# AudioStage.net
KiCad netlist of a schematic drawn in Altium Designer
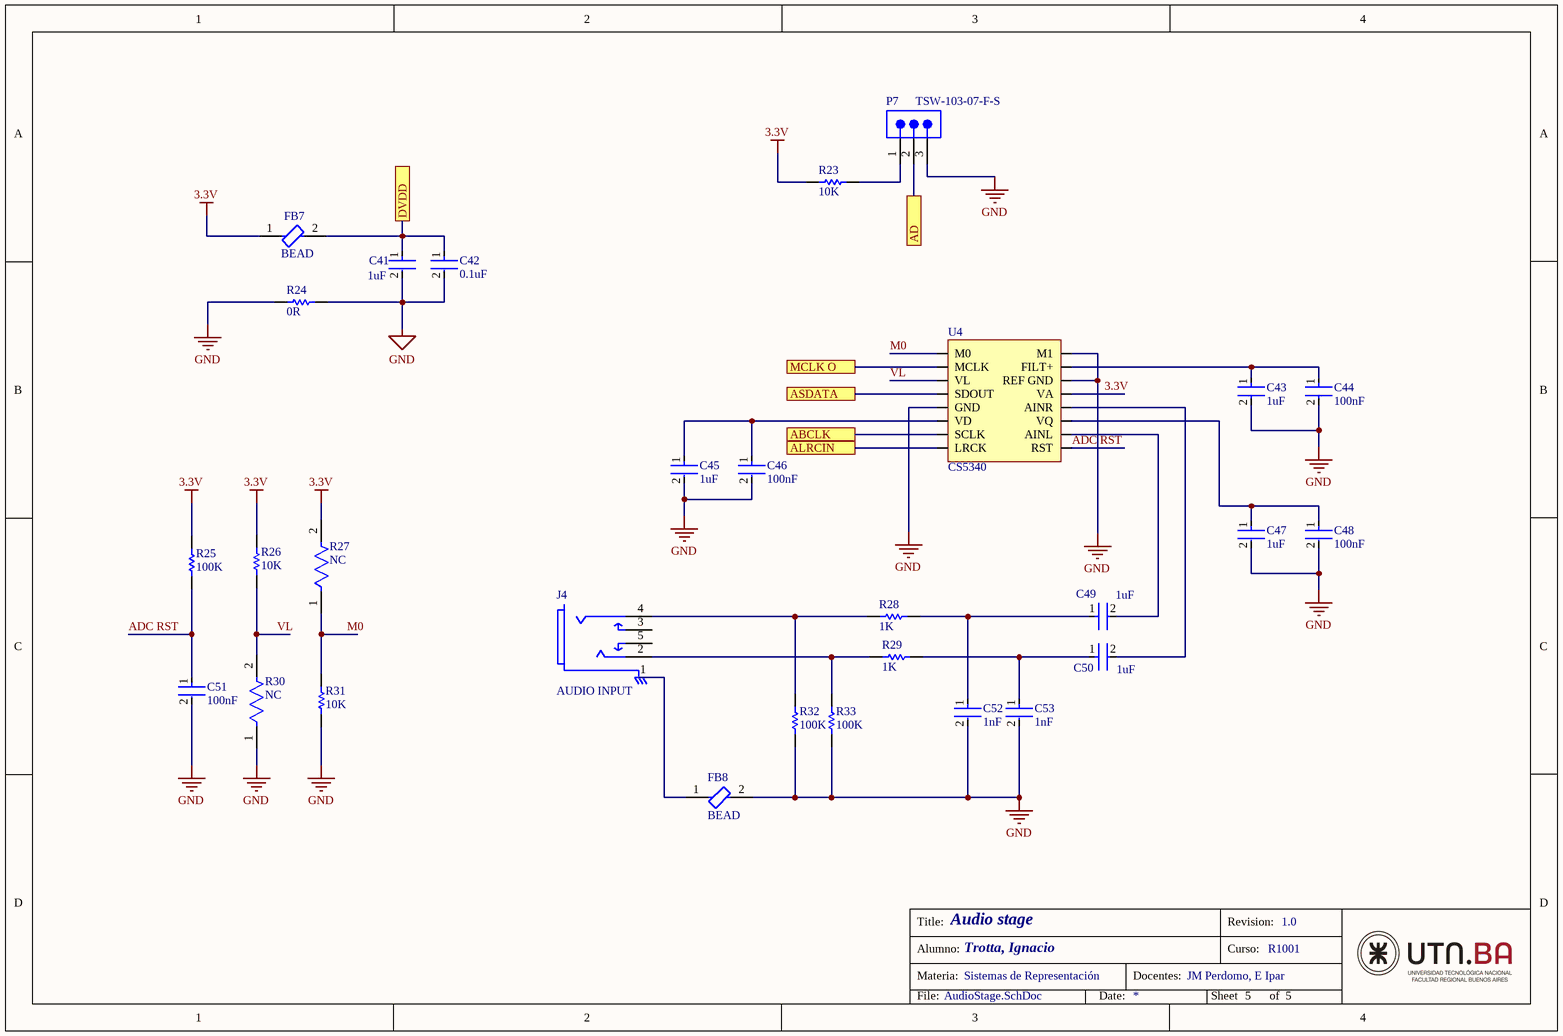
[diagram p0: AudioStage.SchDoc]

(export (version "E")
  (design (tool "Eeschema 10.0.6"))
  (components
    (comp (ref "C41")
      (value "1uF")
      (footprint "FP-CC0603-DA-MFG")
      (description "CAP CER 10000PF 50V X7R 0603")
      (fields (field (name "TOLERANCE") "0.1") (field (name "MANUFACTURER PART NUMBER") "CC0603KRX7R9BB103"))
      (libsource (lib "Altium Content Vault") (part "11868f565c42a9108669ba33697ecf6"))
    )
    (comp (ref "C42")
      (value "0.1uF")
      (footprint "FP-CC0603-DA-MFG")
      (description "CAP CER 10000PF 50V X7R 0603")
      (fields (field (name "TOLERANCE") "0.1") (field (name "MANUFACTURER PART NUMBER") "CC0603KRX7R9BB103"))
      (libsource (lib "Altium Content Vault") (part "11868f565c42a9108669ba33697ecf6"))
    )
    (comp (ref "C43")
      (value "1uF")
      (footprint "FP-CC0603-DA-MFG")
      (description "CAP CER 10000PF 50V X7R 0603")
      (fields (field (name "TOLERANCE") "0.1") (field (name "MANUFACTURER PART NUMBER") "CC0603KRX7R9BB103"))
      (libsource (lib "Altium Content Vault") (part "11868f565c42a9108669ba33697ecf6"))
    )
    (comp (ref "C44")
      (value "100nF")
      (footprint "FP-CC0603-DA-MFG")
      (description "CAP CER 10000PF 50V X7R 0603")
      (fields (field (name "TOLERANCE") "0.1") (field (name "MANUFACTURER PART NUMBER") "CC0603KRX7R9BB103"))
      (libsource (lib "Altium Content Vault") (part "11868f565c42a9108669ba33697ecf6"))
    )
    (comp (ref "C45")
      (value "1uF")
      (footprint "FP-CC0603-DA-MFG")
      (description "CAP CER 10000PF 50V X7R 0603")
      (fields (field (name "TOLERANCE") "0.1") (field (name "MANUFACTURER PART NUMBER") "CC0603KRX7R9BB103"))
      (libsource (lib "Altium Content Vault") (part "11868f565c42a9108669ba33697ecf6"))
    )
    (comp (ref "C46")
      (value "100nF")
      (footprint "FP-CC0603-DA-MFG")
      (description "CAP CER 10000PF 50V X7R 0603")
      (fields (field (name "TOLERANCE") "0.1") (field (name "MANUFACTURER PART NUMBER") "CC0603KRX7R9BB103"))
      (libsource (lib "Altium Content Vault") (part "11868f565c42a9108669ba33697ecf6"))
    )
    (comp (ref "C47")
      (value "1uF")
      (footprint "FP-CC0603-DA-MFG")
      (description "CAP CER 10000PF 50V X7R 0603")
      (fields (field (name "TOLERANCE") "0.1") (field (name "MANUFACTURER PART NUMBER") "CC0603KRX7R9BB103"))
      (libsource (lib "Altium Content Vault") (part "11868f565c42a9108669ba33697ecf6"))
    )
    (comp (ref "C48")
      (value "100nF")
      (footprint "FP-CC0603-DA-MFG")
      (description "CAP CER 10000PF 50V X7R 0603")
      (fields (field (name "TOLERANCE") "0.1") (field (name "MANUFACTURER PART NUMBER") "CC0603KRX7R9BB103"))
      (libsource (lib "Altium Content Vault") (part "11868f565c42a9108669ba33697ecf6"))
    )
    (comp (ref "C49")
      (value "1uF")
      (footprint "FP-CC0603-DA-MFG")
      (description "CAP CER 10000PF 50V X7R 0603")
      (fields (field (name "TOLERANCE") "0.1") (field (name "MANUFACTURER PART NUMBER") "CC0603KRX7R9BB103"))
      (libsource (lib "Altium Content Vault") (part "11868f565c42a9108669ba33697ecf6"))
    )
    (comp (ref "C50")
      (value "1uF")
      (footprint "FP-CC0603-DA-MFG")
      (description "CAP CER 10000PF 50V X7R 0603")
      (fields (field (name "TOLERANCE") "0.1") (field (name "MANUFACTURER PART NUMBER") "CC0603KRX7R9BB103"))
      (libsource (lib "Altium Content Vault") (part "11868f565c42a9108669ba33697ecf6"))
    )
    (comp (ref "C51")
      (value "100nF")
      (footprint "FP-CC0603-DA-MFG")
      (description "CAP CER 10000PF 50V X7R 0603")
      (fields (field (name "TOLERANCE") "0.1") (field (name "MANUFACTURER PART NUMBER") "CC0603KRX7R9BB103"))
      (libsource (lib "Altium Content Vault") (part "11868f565c42a9108669ba33697ecf6"))
    )
    (comp (ref "C52")
      (value "1nF")
      (footprint "FP-CC0603-DA-MFG")
      (description "CAP CER 10000PF 50V X7R 0603")
      (fields (field (name "TOLERANCE") "0.1") (field (name "MANUFACTURER PART NUMBER") "CC0603KRX7R9BB103"))
      (libsource (lib "Altium Content Vault") (part "11868f565c42a9108669ba33697ecf6"))
    )
    (comp (ref "C53")
      (value "1nF")
      (footprint "FP-CC0603-DA-MFG")
      (description "CAP CER 10000PF 50V X7R 0603")
      (fields (field (name "TOLERANCE") "0.1") (field (name "MANUFACTURER PART NUMBER") "CC0603KRX7R9BB103"))
      (libsource (lib "Altium Content Vault") (part "11868f565c42a9108669ba33697ecf6"))
    )
    (comp (ref "FB7")
      (value "BEAD")
      (footprint "FP-BLM18-0_15-t0_8-IPC_B")
      (description "Chip Ferrite Bead, 0603, 75Ω @ 100MHz, 0.3Ω, 25%, 600mA")
      (fields (field (name "TOLERANCE") "25%"))
      (libsource (lib "Altium Content Vault") (part "5f30dd21d616792df468990f7003faa"))
    )
    (comp (ref "FB8")
      (value "BEAD")
      (footprint "FP-BLM18-0_15-t0_8-IPC_B")
      (description "Chip Ferrite Bead, 0603, 75Ω @ 100MHz, 0.3Ω, 25%, 600mA")
      (fields (field (name "TOLERANCE") "25%"))
      (libsource (lib "Altium Content Vault") (part "5f30dd21d616792df468990f7003faa"))
    )
    (comp (ref "J4")
      (value "AUDIO INPUT")
      (footprint "FP-35RAPC4BV4-MFG")
      (description "CONN JACK STEREO 3.5MM R/A")
      (fields (field (name "MANUFACTURER") "Switchcraft") (field (name "OBSOLETE PART") "true"))
      (libsource (lib "Altium Content Vault") (part "75ff47c9dea01840d0d9527457fc737"))
    )
    (comp (ref "P7")
      (value "TSW-103-07-F-S")
      (footprint "SMTC-TSW-103-07-X-S")
      (description "0.025\" SQ Post Header, Through-hole, Vertical, -55 to 125 degC, 2.54 mm Pitch, 3-Pin, Male, RoHS")
      (fields (field (name "MANUFACTURER") "Samtec"))
      (libsource (lib "Altium Content Vault") (part "SMTC-TSW-103-X-X-S-X"))
    )
    (comp (ref "R23")
      (value "10K")
      (footprint "RESC1608X55X25ML10T15")
      (description "Chip Resistor, 100 Ohm, +/- 5%, 50 V, 0603 (1608 Metric), RoHS, Tape and Reel")
      (fields (field (name "MANUFACTURER") "Yageo") (field (name "TOLERANCE") "5%"))
      (libsource (lib "Altium Content Vault") (part "RES-2"))
    )
    (comp (ref "R24")
      (value "0R")
      (footprint "RESC1608X55X25ML10T15")
      (description "Chip Resistor, 100 Ohm, +/- 5%, 50 V, 0603 (1608 Metric), RoHS, Tape and Reel")
      (fields (field (name "MANUFACTURER") "Yageo") (field (name "TOLERANCE") "5%"))
      (libsource (lib "Altium Content Vault") (part "RES-2"))
    )
    (comp (ref "R25")
      (value "100K")
      (footprint "RESC1608X55X25ML10T15")
      (description "Chip Resistor, 100 Ohm, +/- 5%, 50 V, 0603 (1608 Metric), RoHS, Tape and Reel")
      (fields (field (name "MANUFACTURER") "Yageo") (field (name "TOLERANCE") "5%"))
      (libsource (lib "Altium Content Vault") (part "RES-2"))
    )
    (comp (ref "R26")
      (value "10K")
      (footprint "RESC1608X55X25ML10T15")
      (description "Chip Resistor, 100 Ohm, +/- 5%, 50 V, 0603 (1608 Metric), RoHS, Tape and Reel")
      (fields (field (name "MANUFACTURER") "Yageo") (field (name "TOLERANCE") "5%"))
      (libsource (lib "Altium Content Vault") (part "RES-2"))
    )
    (comp (ref "R27")
      (value "NC")
      (footprint "FP-CR0805-MFG")
      (description "Thick Film Chip Resistors 0805 100kΩ 0.125W 5% 200ppm/°C")
      (fields (field (name "TOLERANCE") "5%"))
      (libsource (lib "Altium Content Vault") (part "1029c3af85768c4190bb7ad29bc67b5"))
    )
    (comp (ref "R28")
      (value "1K")
      (footprint "RESC1608X55X25ML10T15")
      (description "Chip Resistor, 0 Ohm, +/- 5%, 0.1 W, -55 to 155 degC, 0603 (1608 Metric), RoHS, Tape and Reel")
      (fields (field (name "TOLERANCE") "5%") (field (name "MANUFACTURER") "Yageo"))
      (libsource (lib "Altium Content Vault") (part "RES-2"))
    )
    (comp (ref "R29")
      (value "1K")
      (footprint "RESC1608X55X25ML10T15")
      (description "Chip Resistor, 0 Ohm, +/- 5%, 0.1 W, -55 to 155 degC, 0603 (1608 Metric), RoHS, Tape and Reel")
      (fields (field (name "TOLERANCE") "5%") (field (name "MANUFACTURER") "Yageo"))
      (libsource (lib "Altium Content Vault") (part "RES-2"))
    )
    (comp (ref "R30")
      (value "NC")
      (footprint "FP-CR0805-MFG")
      (description "Thick Film Chip Resistors 0805 100kΩ 0.125W 5% 200ppm/°C")
      (fields (field (name "TOLERANCE") "5%"))
      (libsource (lib "Altium Content Vault") (part "1029c3af85768c4190bb7ad29bc67b5"))
    )
    (comp (ref "R31")
      (value "10K")
      (footprint "RESC1608X55X25ML10T15")
      (description "Chip Resistor, 100 Ohm, +/- 5%, 50 V, 0603 (1608 Metric), RoHS, Tape and Reel")
      (fields (field (name "MANUFACTURER") "Yageo") (field (name "TOLERANCE") "5%"))
      (libsource (lib "Altium Content Vault") (part "RES-2"))
    )
    (comp (ref "R32")
      (value "100K")
      (footprint "RESC1608X55X25ML10T15")
      (description "Chip Resistor, 100 Ohm, +/- 5%, 50 V, 0603 (1608 Metric), RoHS, Tape and Reel")
      (fields (field (name "MANUFACTURER") "Yageo") (field (name "TOLERANCE") "5%"))
      (libsource (lib "Altium Content Vault") (part "RES-2"))
    )
    (comp (ref "R33")
      (value "100K")
      (footprint "RESC1608X55X25ML10T15")
      (description "Chip Resistor, 100 Ohm, +/- 5%, 50 V, 0603 (1608 Metric), RoHS, Tape and Reel")
      (fields (field (name "MANUFACTURER") "Yageo") (field (name "TOLERANCE") "5%"))
      (libsource (lib "Altium Content Vault") (part "RES-2"))
    )
    (comp (ref "U4")
      (value "CS5340")
      (footprint "pcb-libs:TSSOP-16L")
      (description "101dB, 192kHz, Multi-Bit Audio A/D Converter")
      (libsource (lib "sch-libs") (part "CS5340_Trotta"))
    )
  )
  (nets
    (net (code "1") (name "/ABCLK") (class "Default")
      (node (ref "U4") (pin "7") (pinfunction "SCLK_7") (pintype "passive"))
    )
    (net (code "2") (name "/AD") (class "Default")
      (node (ref "P7") (pin "2") (pinfunction "2_2") (pintype "passive"))
    )
    (net (code "3") (name "/ADC RST") (class "Default")
      (node (ref "C51") (pin "1") (pinfunction "1_1") (pintype "passive"))
      (node (ref "R25") (pin "1") (pinfunction "1_1") (pintype "passive"))
      (node (ref "U4") (pin "9") (pinfunction "RST_9") (pintype "passive"))
    )
    (net (code "4") (name "/ALRCIN") (class "Default")
      (node (ref "U4") (pin "8") (pinfunction "LRCK_8") (pintype "passive"))
    )
    (net (code "5") (name "/ASDATA") (class "Default")
      (node (ref "U4") (pin "4") (pinfunction "SDOUT_4") (pintype "passive"))
    )
    (net (code "6") (name "/DVDD") (class "Default")
      (node (ref "C41") (pin "1") (pinfunction "1_1") (pintype "passive"))
      (node (ref "C42") (pin "1") (pinfunction "1_1") (pintype "passive"))
      (node (ref "FB7") (pin "2") (pinfunction "2_2") (pintype "passive"))
    )
    (net (code "7") (name "/M0") (class "Default")
      (node (ref "R27") (pin "1") (pinfunction "1_1") (pintype "passive"))
      (node (ref "R31") (pin "2") (pinfunction "2_2") (pintype "passive"))
      (node (ref "U4") (pin "1") (pinfunction "M0_1") (pintype "passive"))
    )
    (net (code "8") (name "/MCLK O") (class "Default")
      (node (ref "U4") (pin "2") (pinfunction "MCLK_2") (pintype "passive"))
    )
    (net (code "9") (name "/VL") (class "Default")
      (node (ref "R26") (pin "1") (pinfunction "1_1") (pintype "passive"))
      (node (ref "R30") (pin "2") (pinfunction "2_2") (pintype "passive"))
      (node (ref "U4") (pin "3") (pinfunction "VL_3") (pintype "passive"))
    )
    (net (code "10") (name "3.3V") (class "Default")
      (node (ref "FB7") (pin "1") (pinfunction "1_1") (pintype "passive"))
      (node (ref "R23") (pin "1") (pinfunction "1_1") (pintype "passive"))
      (node (ref "R25") (pin "2") (pinfunction "2_2") (pintype "passive"))
      (node (ref "R26") (pin "2") (pinfunction "2_2") (pintype "passive"))
      (node (ref "R27") (pin "2") (pinfunction "2_2") (pintype "passive"))
      (node (ref "U4") (pin "13") (pinfunction "VA_13") (pintype "passive"))
    )
    (net (code "11") (name "GND") (class "Default")
      (node (ref "C41") (pin "2") (pinfunction "2_2") (pintype "passive"))
      (node (ref "C42") (pin "2") (pinfunction "2_2") (pintype "passive"))
      (node (ref "C43") (pin "2") (pinfunction "2_2") (pintype "passive"))
      (node (ref "C44") (pin "2") (pinfunction "2_2") (pintype "passive"))
      (node (ref "C45") (pin "2") (pinfunction "2_2") (pintype "passive"))
      (node (ref "C46") (pin "2") (pinfunction "2_2") (pintype "passive"))
      (node (ref "C47") (pin "2") (pinfunction "2_2") (pintype "passive"))
      (node (ref "C48") (pin "2") (pinfunction "2_2") (pintype "passive"))
      (node (ref "C51") (pin "2") (pinfunction "2_2") (pintype "passive"))
      (node (ref "C52") (pin "2") (pinfunction "2_2") (pintype "passive"))
      (node (ref "C53") (pin "2") (pinfunction "2_2") (pintype "passive"))
      (node (ref "FB8") (pin "2") (pinfunction "2_2") (pintype "passive"))
      (node (ref "P7") (pin "3") (pinfunction "3_3") (pintype "passive"))
      (node (ref "R24") (pin "1") (pinfunction "1_1") (pintype "passive"))
      (node (ref "R24") (pin "2") (pinfunction "2_2") (pintype "passive"))
      (node (ref "R30") (pin "1") (pinfunction "1_1") (pintype "passive"))
      (node (ref "R31") (pin "1") (pinfunction "1_1") (pintype "passive"))
      (node (ref "R32") (pin "1") (pinfunction "1_1") (pintype "passive"))
      (node (ref "R33") (pin "1") (pinfunction "1_1") (pintype "passive"))
      (node (ref "U4") (pin "14") (pinfunction "REF_GND_14") (pintype "passive"))
      (node (ref "U4") (pin "16") (pinfunction "M1_16") (pintype "passive"))
      (node (ref "U4") (pin "5") (pinfunction "GND_5") (pintype "passive"))
    )
    (net (code "12") (name "Net-(C49-Pad1)") (class "Default")
      (node (ref "C49") (pin "1") (pinfunction "1_1") (pintype "passive"))
      (node (ref "C52") (pin "1") (pinfunction "1_1") (pintype "passive"))
      (node (ref "R28") (pin "2") (pinfunction "2_2") (pintype "passive"))
    )
    (net (code "13") (name "Net-(C50-Pad1)") (class "Default")
      (node (ref "C50") (pin "1") (pinfunction "1_1") (pintype "passive"))
      (node (ref "C53") (pin "1") (pinfunction "1_1") (pintype "passive"))
      (node (ref "R29") (pin "2") (pinfunction "2_2") (pintype "passive"))
    )
    (net (code "14") (name "Net-(FB8-Pad1)") (class "Default")
      (node (ref "FB8") (pin "1") (pinfunction "1_1") (pintype "passive"))
      (node (ref "J4") (pin "1") (pinfunction "1_1") (pintype "passive"))
    )
    (net (code "15") (name "Net-(J4-Pad2)") (class "Default")
      (node (ref "J4") (pin "2") (pinfunction "2_2") (pintype "passive"))
      (node (ref "R29") (pin "1") (pinfunction "1_1") (pintype "passive"))
      (node (ref "R33") (pin "2") (pinfunction "2_2") (pintype "passive"))
    )
    (net (code "16") (name "Net-(J4-Pad4)") (class "Default")
      (node (ref "J4") (pin "4") (pinfunction "4_4") (pintype "passive"))
      (node (ref "R28") (pin "1") (pinfunction "1_1") (pintype "passive"))
      (node (ref "R32") (pin "2") (pinfunction "2_2") (pintype "passive"))
    )
    (net (code "17") (name "Net-(P7-Pad1)") (class "Default")
      (node (ref "P7") (pin "1") (pinfunction "1_1") (pintype "passive"))
      (node (ref "R23") (pin "2") (pinfunction "2_2") (pintype "passive"))
    )
    (net (code "18") (name "Net-(U4-AINL)") (class "Default")
      (node (ref "C49") (pin "2") (pinfunction "2_2") (pintype "passive"))
      (node (ref "U4") (pin "10") (pinfunction "AINL_10") (pintype "passive"))
    )
    (net (code "19") (name "Net-(U4-AINR)") (class "Default")
      (node (ref "C50") (pin "2") (pinfunction "2_2") (pintype "passive"))
      (node (ref "U4") (pin "12") (pinfunction "AINR_12") (pintype "passive"))
    )
    (net (code "20") (name "Net-(U4-FILT+)") (class "Default")
      (node (ref "C43") (pin "1") (pinfunction "1_1") (pintype "passive"))
      (node (ref "C44") (pin "1") (pinfunction "1_1") (pintype "passive"))
      (node (ref "U4") (pin "15") (pinfunction "FILT+_15") (pintype "passive"))
    )
    (net (code "21") (name "Net-(U4-VD)") (class "Default")
      (node (ref "C45") (pin "1") (pinfunction "1_1") (pintype "passive"))
      (node (ref "C46") (pin "1") (pinfunction "1_1") (pintype "passive"))
      (node (ref "U4") (pin "6") (pinfunction "VD_6") (pintype "passive"))
    )
    (net (code "22") (name "Net-(U4-VQ)") (class "Default")
      (node (ref "C47") (pin "1") (pinfunction "1_1") (pintype "passive"))
      (node (ref "C48") (pin "1") (pinfunction "1_1") (pintype "passive"))
      (node (ref "U4") (pin "11") (pinfunction "VQ_11") (pintype "passive"))
    )
    (net (code "23") (name "unconnected-(J4-Pad3)") (class "Default")
      (node (ref "J4") (pin "3") (pinfunction "3_3") (pintype "passive"))
    )
    (net (code "24") (name "unconnected-(J4-Pad5)") (class "Default")
      (node (ref "J4") (pin "5") (pinfunction "5_5") (pintype "passive"))
    )
  )
)
